# eVV_Radio.net
KiCad netlist of a schematic drawn in Altium Designer
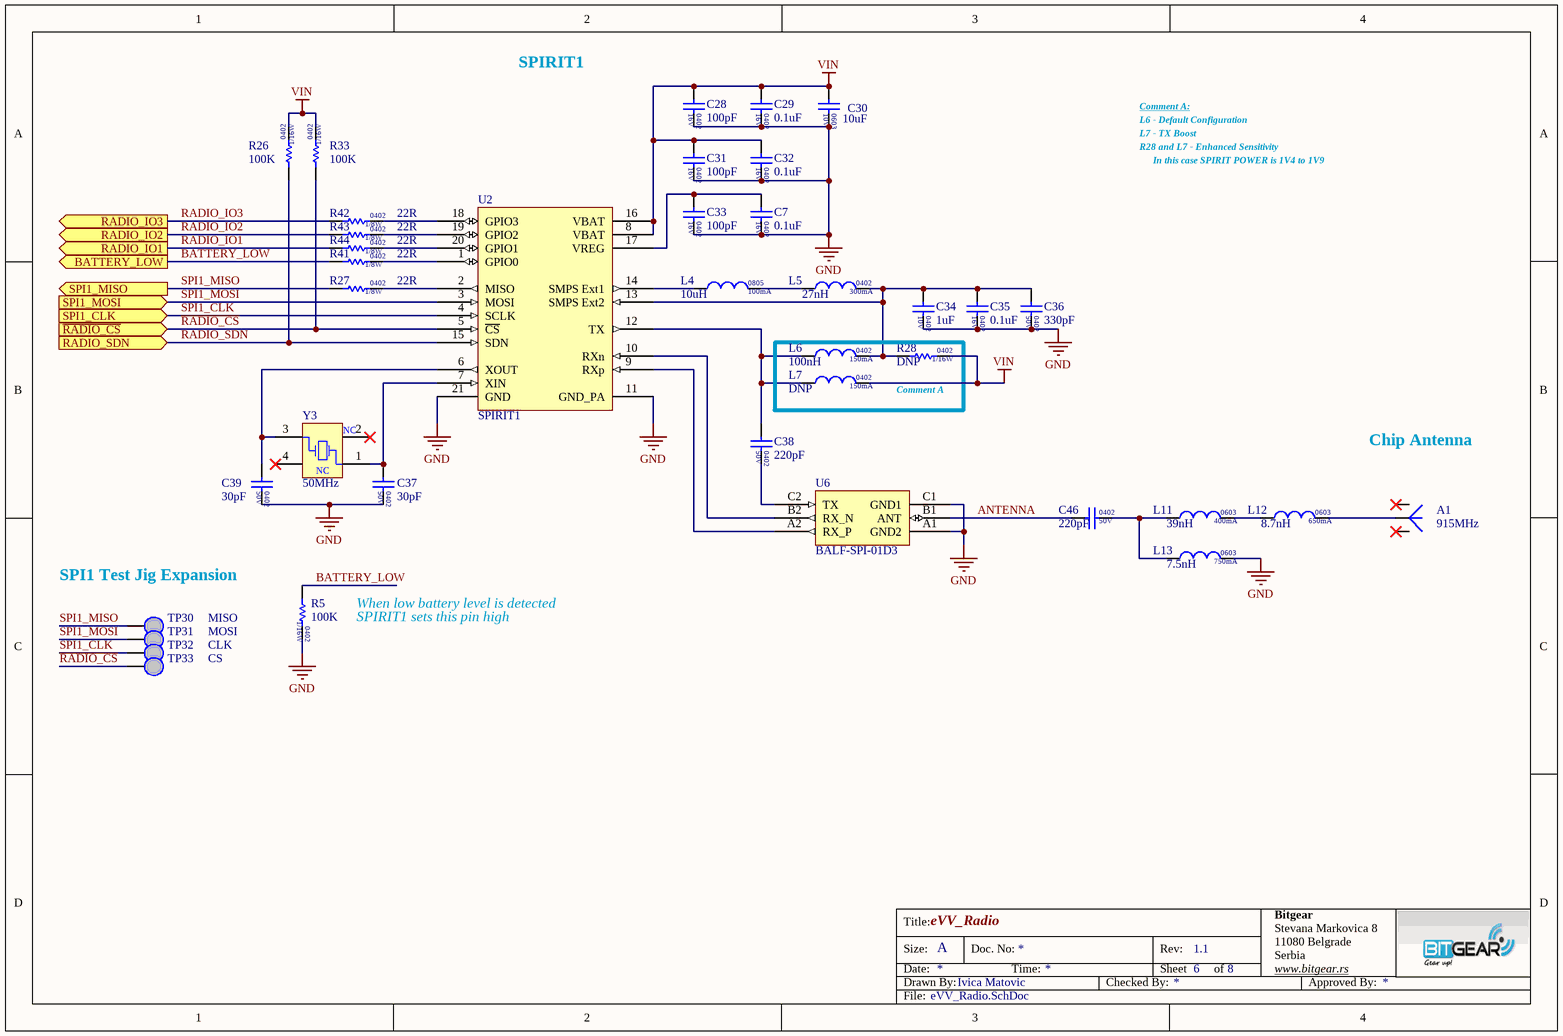
[diagram p0: eVV_Radio.SchDoc]

(export (version "E")
  (design (tool "Eeschema 10.0.6"))
  (components
    (comp (ref "A1")
      (value "915MHz")
      (footprint "MITSUBISHI_AM11DG-ST01")
      (description "Mitscubishi SMD Chip Antenna 3.0X10.5mm")
      (fields (field (name "MANUFACTURER") "Mitsubishi Materials"))
      (libsource (lib "ecoVENTV") (part "AM11DG-ST01"))
    )
    (comp (ref "C7")
      (value "0.1uF")
      (footprint "CAPC1005X60N")
      (description "CAP CER 0.1UF 0402 (1005) 16V X7R 10%")
      (fields (field (name "MANUFACTURER") "Murata Electronics North America"))
      (libsource (lib "ecoVENTV") (part "Cap-1005 (0402) CER 0.1UF 16V X7R 10%"))
    )
    (comp (ref "C28")
      (value "100pF")
      (footprint "CAPC1005X60N")
      (description "CAP CER 100PF 0402 (1005) 16V C0G 10%")
      (fields (field (name "MANUFACTURER") "Kemet"))
      (libsource (lib "ecoVENTV") (part "Cap-1005 (0402) CER 100PF 16V C0G 10%"))
    )
    (comp (ref "C29")
      (value "0.1uF")
      (footprint "CAPC1005X60N")
      (description "CAP CER 0.1UF 0402 (1005) 16V X7R 10%")
      (fields (field (name "MANUFACTURER") "Murata Electronics North America"))
      (libsource (lib "ecoVENTV") (part "Cap-1005 (0402) CER 0.1UF 16V X7R 10%"))
    )
    (comp (ref "C30")
      (value "10uF")
      (footprint "CAPC1608X95N")
      (description "Capacitor Ceramic 10uF 1608 (0603) 10V X5R 20%")
      (fields (field (name "MANUFACTURER") "Taiyo Yuden"))
      (libsource (lib "ecoVENTV") (part "Cap-1608 (0603) CER 10uF 10V X5R 20%"))
    )
    (comp (ref "C31")
      (value "100pF")
      (footprint "CAPC1005X60N")
      (description "CAP CER 100PF 0402 (1005) 16V C0G 10%")
      (fields (field (name "MANUFACTURER") "Kemet"))
      (libsource (lib "ecoVENTV") (part "Cap-1005 (0402) CER 100PF 16V C0G 10%"))
    )
    (comp (ref "C32")
      (value "0.1uF")
      (footprint "CAPC1005X60N")
      (description "CAP CER 0.1UF 0402 (1005) 16V X7R 10%")
      (fields (field (name "MANUFACTURER") "Murata Electronics North America"))
      (libsource (lib "ecoVENTV") (part "Cap-1005 (0402) CER 0.1UF 16V X7R 10%"))
    )
    (comp (ref "C33")
      (value "100pF")
      (footprint "CAPC1005X60N")
      (description "CAP CER 100PF 0402 (1005) 16V C0G 10%")
      (fields (field (name "MANUFACTURER") "Kemet"))
      (libsource (lib "ecoVENTV") (part "Cap-1005 (0402) CER 100PF 16V C0G 10%"))
    )
    (comp (ref "C34")
      (value "1uF")
      (footprint "CAPC1005X60N")
      (description "Cap-1005 (0402) CER 1uF 10V X5R 10%")
      (fields (field (name "MANUFACTURER") "Murata Electronics North America"))
      (libsource (lib "ecoVENTV") (part "Cap-1005 (0402) CER 1uF 10V X5R 10%"))
    )
    (comp (ref "C35")
      (value "0.1uF")
      (footprint "CAPC1005X60N")
      (description "CAP CER 0.1UF 0402 (1005) 16V X7R 10%")
      (fields (field (name "MANUFACTURER") "Murata Electronics North America"))
      (libsource (lib "ecoVENTV") (part "Cap-1005 (0402) CER 0.1UF 16V X7R 10%"))
    )
    (comp (ref "C36")
      (value "330pF")
      (footprint "CAPC1005X60N")
      (description "Cap-1005 (0402) CER 330pF 50V C0G 5%")
      (fields (field (name "MANUFACTURER") "Murata Electronics North America"))
      (libsource (lib "ecoVENTV") (part "Cap-1005 (0402) CER 330pF 50V C0G 5%"))
    )
    (comp (ref "C37")
      (value "30pF")
      (footprint "CAPC1005X60N")
      (description "CAP CER 30PF 50V 5% NP0 0402 (1005)")
      (fields (field (name "MANUFACTURER") "Murata Electronics North America"))
      (libsource (lib "ecoVENTV") (part "Cap-1005 (0402) CER 30pF 50V NP0 5%"))
    )
    (comp (ref "C38")
      (value "220pF")
      (footprint "CAPC1005X60N")
      (description "Cap-1005 (0402) CER 220pF 50V C0G 5%")
      (fields (field (name "MANUFACTURER") "Murata Electronics North America"))
      (libsource (lib "ecoVENTV") (part "Cap-1005 (0402) CER 220pF 50V C0G 5%"))
    )
    (comp (ref "C39")
      (value "30pF")
      (footprint "CAPC1005X60N")
      (description "CAP CER 30PF 50V 5% NP0 0402 (1005)")
      (fields (field (name "MANUFACTURER") "Murata Electronics North America"))
      (libsource (lib "ecoVENTV") (part "Cap-1005 (0402) CER 30pF 50V NP0 5%"))
    )
    (comp (ref "C46")
      (value "220pF")
      (footprint "CAPC1005X60N")
      (description "Cap-1005 (0402) CER 220pF 50V C0G 5%")
      (fields (field (name "MANUFACTURER") "Murata Electronics North America"))
      (libsource (lib "ecoVENTV") (part "Cap-1005 (0402) CER 220pF 50V C0G 5%"))
    )
    (comp (ref "L4")
      (value "10uH")
      (footprint "INDC2012X85N")
      (description "Inductor 10uH 100mA 20% 0805 SMD")
      (fields (field (name "MANUFACTURER") "Murata"))
      (libsource (lib "ecoVENTV") (part "Ind-2012 (0805) 10uH 100mA 20%"))
    )
    (comp (ref "L5")
      (value "27nH")
      (footprint "INDC1005X60N")
      (description "Inductor 27nH 300mA 5% 0402 SMD")
      (fields (field (name "MANUFACTURER") "Murata Electronics North America"))
      (libsource (lib "ecoVENTV") (part "Ind-1005 (0402) 27nH 300mA 5%"))
    )
    (comp (ref "L6")
      (value "100nH")
      (footprint "INDC1005X60N")
      (description "Inductor 100nH 150mA 5% 0402 SMD")
      (fields (field (name "MANUFACTURER") "Murata Electronics North America"))
      (libsource (lib "ecoVENTV") (part "Ind-1005 (0402) 100nH 150mA 5%"))
    )
    (comp (ref "L7")
      (value "DNP")
      (footprint "INDC1005X60N")
      (description "Inductor 100nH 150mA 5% 0402 SMD")
      (fields (field (name "MANUFACTURER") "Murata Electronics North America"))
      (libsource (lib "ecoVENTV") (part "Ind-1005 (0402) 100nH 150mA 5%"))
    )
    (comp (ref "L11")
      (value "39nH")
      (footprint "MURATA_LQW18A")
      (description "Inductor 39nH 400mA 2% 0603 SMD Wirewound")
      (fields (field (name "MANUFACTURER") "Murata Electronics North America"))
      (libsource (lib "ecoVENTV") (part "Ind-1608 (0603) 39nH 400mA 2%"))
    )
    (comp (ref "L12")
      (value "8.7nH")
      (footprint "MURATA_LQW18A")
      (description "Inductor 8.7nH 650mA 0.5nH 0603 SMD Wirewound")
      (fields (field (name "MANUFACTURER") "Murata Electronics North America"))
      (libsource (lib "ecoVENTV") (part "Ind-1608 (0603) 8.7nH 650mA 0.5nH"))
    )
    (comp (ref "L13")
      (value "7.5nH")
      (footprint "MURATA_LQW18A")
      (description "Inductor 7.5nH 750mA 0.5nH 0603 SMD Wirewound")
      (fields (field (name "MANUFACTURER") "Murata Electronics North America"))
      (libsource (lib "ecoVENTV") (part "Ind-1608 (0603) 7.5nH 750mA 0.5nH"))
    )
    (comp (ref "R5")
      (value "100K")
      (footprint "RESC1005X40AN")
      (description "Res-1005 (0402) 100 KOhm 1/16W 1%")
      (fields (field (name "MANUFACTURER") "Vishay Dale"))
      (libsource (lib "ecoVENTV") (part "Res-1005 (0402) 100 KOhm 1/16W 1%"))
    )
    (comp (ref "R26")
      (value "100K")
      (footprint "RESC1005X40AN")
      (description "Res-1005 (0402) 100 KOhm 1/16W 1%")
      (fields (field (name "MANUFACTURER") "Vishay Dale"))
      (libsource (lib "ecoVENTV") (part "Res-1005 (0402) 100 KOhm 1/16W 1%"))
    )
    (comp (ref "R27")
      (value "22R")
      (footprint "RESC1005X40AN")
      (description "Res-1005 (0402) 22 Ohm 1/8W 1%")
      (fields (field (name "MANUFACTURER") "Vishay Dale"))
      (libsource (lib "ecoVENTV") (part "Res-1005 (0402) 22 Ohm 1/8W 1%"))
    )
    (comp (ref "R28")
      (value "DNP")
      (footprint "RESC1005X40AN")
      (description "Res-1005 (0402) 0 Ohm 1/16W")
      (fields (field (name "MANUFACTURER") "Stackpole Electronics Inc"))
      (libsource (lib "ecoVENTV") (part "Res-1005 (0402) 0 Ohm 1/16W"))
    )
    (comp (ref "R33")
      (value "100K")
      (footprint "RESC1005X40AN")
      (description "Res-1005 (0402) 100 KOhm 1/16W 1%")
      (fields (field (name "MANUFACTURER") "Vishay Dale"))
      (libsource (lib "ecoVENTV") (part "Res-1005 (0402) 100 KOhm 1/16W 1%"))
    )
    (comp (ref "R41")
      (value "22R")
      (footprint "RESC1005X40AN")
      (description "Res-1005 (0402) 22 Ohm 1/8W 1%")
      (fields (field (name "MANUFACTURER") "Vishay Dale"))
      (libsource (lib "ecoVENTV") (part "Res-1005 (0402) 22 Ohm 1/8W 1%"))
    )
    (comp (ref "R42")
      (value "22R")
      (footprint "RESC1005X40AN")
      (description "Res-1005 (0402) 22 Ohm 1/8W 1%")
      (fields (field (name "MANUFACTURER") "Vishay Dale"))
      (libsource (lib "ecoVENTV") (part "Res-1005 (0402) 22 Ohm 1/8W 1%"))
    )
    (comp (ref "R43")
      (value "22R")
      (footprint "RESC1005X40AN")
      (description "Res-1005 (0402) 22 Ohm 1/8W 1%")
      (fields (field (name "MANUFACTURER") "Vishay Dale"))
      (libsource (lib "ecoVENTV") (part "Res-1005 (0402) 22 Ohm 1/8W 1%"))
    )
    (comp (ref "R44")
      (value "22R")
      (footprint "RESC1005X40AN")
      (description "Res-1005 (0402) 22 Ohm 1/8W 1%")
      (fields (field (name "MANUFACTURER") "Vishay Dale"))
      (libsource (lib "ecoVENTV") (part "Res-1005 (0402) 22 Ohm 1/8W 1%"))
    )
    (comp (ref "TP30")
      (value "MISO")
      (footprint "TEST_POINT_1MM")
      (description "Test point")
      (libsource (lib "ecoVENTV") (part "TP"))
    )
    (comp (ref "TP31")
      (value "MOSI")
      (footprint "TEST_POINT_1MM")
      (description "Test point")
      (libsource (lib "ecoVENTV") (part "TP"))
    )
    (comp (ref "TP32")
      (value "CLK")
      (footprint "TEST_POINT_1MM")
      (description "Test point")
      (libsource (lib "ecoVENTV") (part "TP"))
    )
    (comp (ref "TP33")
      (value "CS")
      (footprint "TEST_POINT_1MM")
      (description "Test point")
      (libsource (lib "ecoVENTV") (part "TP"))
    )
    (comp (ref "U2")
      (value "SPIRIT1")
      (footprint "QFN50P400X400X100-21N")
      (description "Low data rate, low power sub-1GHZ transceiver")
      (fields (field (name "MANUFACTURER") "ST Microelectronics"))
      (libsource (lib "ecoVENTV") (part "SPIRIT1"))
    )
    (comp (ref "U6")
      (value "BALF-SPI-01D3")
      (footprint "STM_BALF_SPI")
      (description "50 Ohm Balun to Spirit1 With Integrated Harmonic Filter")
      (fields (field (name "MANUFACTURER") "ST Microelectronics"))
      (libsource (lib "ecoVENTV") (part "BALF-SPI-01D3"))
    )
    (comp (ref "Y3")
      (value "50MHz")
      (footprint "AVX_CX3225GB50")
      (description "Crystal 50.000MHZ 3.2mm x 2.5mm 18pF")
      (fields (field (name "MANUFACTURER") "AVX Corp."))
      (libsource (lib "ecoVENTV") (part "CX3225GB50"))
    )
  )
  (nets
    (net (code "1") (name "/ANTENNA") (class "Default")
      (node (ref "C46") (pin "1") (pinfunction "1_1") (pintype "passive"))
      (node (ref "U6") (pin "B1") (pinfunction "ANT_B1") (pintype "bidirectional"))
    )
    (net (code "2") (name "/BATTERY_LOW") (class "Default")
      (node (ref "R41") (pin "2") (pinfunction "2_2") (pintype "passive"))
      (node (ref "R5") (pin "2") (pinfunction "2_2") (pintype "passive"))
    )
    (net (code "3") (name "/RADIO_IO1") (class "Default")
      (node (ref "R44") (pin "2") (pinfunction "2_2") (pintype "passive"))
    )
    (net (code "4") (name "/RADIO_IO2") (class "Default")
      (node (ref "R43") (pin "2") (pinfunction "2_2") (pintype "passive"))
    )
    (net (code "5") (name "/RADIO_IO3") (class "Default")
      (node (ref "R42") (pin "2") (pinfunction "2_2") (pintype "passive"))
    )
    (net (code "6") (name "/RADIO_SDN") (class "Default")
      (node (ref "R26") (pin "2") (pinfunction "2_2") (pintype "passive"))
      (node (ref "U2") (pin "15") (pinfunction "SDN_15") (pintype "input"))
    )
    (net (code "7") (name "/SPI1_CLK") (class "Default")
      (node (ref "TP32") (pin "1") (pinfunction "1_1") (pintype "passive"))
      (node (ref "U2") (pin "4") (pinfunction "SCLK_4") (pintype "input"))
    )
    (net (code "8") (name "/SPI1_MISO") (class "Default")
      (node (ref "R27") (pin "2") (pinfunction "2_2") (pintype "passive"))
      (node (ref "TP30") (pin "1") (pinfunction "1_1") (pintype "passive"))
    )
    (net (code "9") (name "/SPI1_MOSI") (class "Default")
      (node (ref "TP31") (pin "1") (pinfunction "1_1") (pintype "passive"))
      (node (ref "U2") (pin "3") (pinfunction "MOSI_3") (pintype "input"))
    )
    (net (code "10") (name "/~{RADIO_CS}") (class "Default")
      (node (ref "R33") (pin "2") (pinfunction "2_2") (pintype "passive"))
      (node (ref "TP33") (pin "1") (pinfunction "1_1") (pintype "passive"))
      (node (ref "U2") (pin "5") (pinfunction "~{CS}_5") (pintype "input"))
    )
    (net (code "11") (name "GND") (class "Default")
      (node (ref "C28") (pin "2") (pinfunction "2_2") (pintype "passive"))
      (node (ref "C29") (pin "2") (pinfunction "2_2") (pintype "passive"))
      (node (ref "C30") (pin "2") (pinfunction "2_2") (pintype "passive"))
      (node (ref "C31") (pin "2") (pinfunction "2_2") (pintype "passive"))
      (node (ref "C32") (pin "2") (pinfunction "2_2") (pintype "passive"))
      (node (ref "C33") (pin "2") (pinfunction "2_2") (pintype "passive"))
      (node (ref "C34") (pin "2") (pinfunction "2_2") (pintype "passive"))
      (node (ref "C35") (pin "2") (pinfunction "2_2") (pintype "passive"))
      (node (ref "C36") (pin "2") (pinfunction "2_2") (pintype "passive"))
      (node (ref "C37") (pin "2") (pinfunction "2_2") (pintype "passive"))
      (node (ref "C39") (pin "2") (pinfunction "2_2") (pintype "passive"))
      (node (ref "C7") (pin "2") (pinfunction "2_2") (pintype "passive"))
      (node (ref "L13") (pin "2") (pinfunction "2_2") (pintype "passive"))
      (node (ref "R5") (pin "1") (pinfunction "1_1") (pintype "passive"))
      (node (ref "U2") (pin "11") (pinfunction "GND_PA_11") (pintype "power_in"))
      (node (ref "U2") (pin "21") (pinfunction "GND_21") (pintype "power_in"))
      (node (ref "U6") (pin "A1") (pinfunction "GND2_A1") (pintype "power_in"))
      (node (ref "U6") (pin "C1") (pinfunction "GND1_C1") (pintype "power_in"))
    )
    (net (code "12") (name "Net-(A1-Pad1)") (class "Default")
      (node (ref "A1") (pin "1") (pinfunction "1_1") (pintype "passive"))
      (node (ref "L12") (pin "2") (pinfunction "2_2") (pintype "passive"))
    )
    (net (code "13") (name "Net-(C46-Pad2)") (class "Default")
      (node (ref "C46") (pin "2") (pinfunction "2_2") (pintype "passive"))
      (node (ref "L11") (pin "1") (pinfunction "1_1") (pintype "passive"))
      (node (ref "L13") (pin "1") (pinfunction "1_1") (pintype "passive"))
    )
    (net (code "14") (name "Net-(L4-Pad2)") (class "Default")
      (node (ref "L4") (pin "2") (pinfunction "2_2") (pintype "passive"))
      (node (ref "L5") (pin "1") (pinfunction "1_1") (pintype "passive"))
    )
    (net (code "15") (name "Net-(L11-Pad2)") (class "Default")
      (node (ref "L11") (pin "2") (pinfunction "2_2") (pintype "passive"))
      (node (ref "L12") (pin "1") (pinfunction "1_1") (pintype "passive"))
    )
    (net (code "16") (name "Net-(U2-GPIO0)") (class "Default")
      (node (ref "R41") (pin "1") (pinfunction "1_1") (pintype "passive"))
      (node (ref "U2") (pin "1") (pinfunction "GPIO0_1") (pintype "bidirectional"))
    )
    (net (code "17") (name "Net-(U2-GPIO1)") (class "Default")
      (node (ref "R44") (pin "1") (pinfunction "1_1") (pintype "passive"))
      (node (ref "U2") (pin "20") (pinfunction "GPIO1_20") (pintype "bidirectional"))
    )
    (net (code "18") (name "Net-(U2-GPIO2)") (class "Default")
      (node (ref "R43") (pin "1") (pinfunction "1_1") (pintype "passive"))
      (node (ref "U2") (pin "19") (pinfunction "GPIO2_19") (pintype "bidirectional"))
    )
    (net (code "19") (name "Net-(U2-GPIO3)") (class "Default")
      (node (ref "R42") (pin "1") (pinfunction "1_1") (pintype "passive"))
      (node (ref "U2") (pin "18") (pinfunction "GPIO3_18") (pintype "bidirectional"))
    )
    (net (code "20") (name "Net-(U2-MISO)") (class "Default")
      (node (ref "R27") (pin "1") (pinfunction "1_1") (pintype "passive"))
      (node (ref "U2") (pin "2") (pinfunction "MISO_2") (pintype "output"))
    )
    (net (code "21") (name "Net-(U2-RXn)") (class "Default")
      (node (ref "U2") (pin "10") (pinfunction "RXn_10") (pintype "input"))
      (node (ref "U6") (pin "B2") (pinfunction "RX_N_B2") (pintype "output"))
    )
    (net (code "22") (name "Net-(U2-RXp)") (class "Default")
      (node (ref "U2") (pin "9") (pinfunction "RXp_9") (pintype "input"))
      (node (ref "U6") (pin "A2") (pinfunction "RX_P_A2") (pintype "output"))
    )
    (net (code "23") (name "Net-(U2-SMPS_Ext1)") (class "Default")
      (node (ref "L4") (pin "1") (pinfunction "1_1") (pintype "passive"))
      (node (ref "U2") (pin "14") (pinfunction "SMPS_Ext1_14") (pintype "output"))
    )
    (net (code "24") (name "Net-(U2-SMPS_Ext2)") (class "Default")
      (node (ref "C34") (pin "1") (pinfunction "1_1") (pintype "passive"))
      (node (ref "C35") (pin "1") (pinfunction "1_1") (pintype "passive"))
      (node (ref "C36") (pin "1") (pinfunction "1_1") (pintype "passive"))
      (node (ref "L5") (pin "2") (pinfunction "2_2") (pintype "passive"))
      (node (ref "L6") (pin "2") (pinfunction "2_2") (pintype "passive"))
      (node (ref "R28") (pin "2") (pinfunction "2_2") (pintype "passive"))
      (node (ref "U2") (pin "13") (pinfunction "SMPS_Ext2_13") (pintype "input"))
    )
    (net (code "25") (name "Net-(U2-TX)") (class "Default")
      (node (ref "C38") (pin "1") (pinfunction "1_1") (pintype "passive"))
      (node (ref "L6") (pin "1") (pinfunction "1_1") (pintype "passive"))
      (node (ref "L7") (pin "1") (pinfunction "1_1") (pintype "passive"))
      (node (ref "U2") (pin "12") (pinfunction "TX_12") (pintype "output"))
    )
    (net (code "26") (name "Net-(U2-VREG)") (class "Default")
      (node (ref "C33") (pin "1") (pinfunction "1_1") (pintype "passive"))
      (node (ref "C7") (pin "1") (pinfunction "1_1") (pintype "passive"))
      (node (ref "U2") (pin "17") (pinfunction "VREG_17") (pintype "power_in"))
    )
    (net (code "27") (name "Net-(U2-XIN)") (class "Default")
      (node (ref "C37") (pin "1") (pinfunction "1_1") (pintype "passive"))
      (node (ref "U2") (pin "7") (pinfunction "XIN_7") (pintype "input"))
      (node (ref "Y3") (pin "1") (pinfunction "OSC1_1") (pintype "passive"))
    )
    (net (code "28") (name "Net-(U2-XOUT)") (class "Default")
      (node (ref "C39") (pin "1") (pinfunction "1_1") (pintype "passive"))
      (node (ref "U2") (pin "6") (pinfunction "XOUT_6") (pintype "output"))
      (node (ref "Y3") (pin "3") (pinfunction "OSC2_3") (pintype "passive"))
    )
    (net (code "29") (name "Net-(U6-TX)") (class "Default")
      (node (ref "C38") (pin "2") (pinfunction "2_2") (pintype "passive"))
      (node (ref "U6") (pin "C2") (pinfunction "TX_C2") (pintype "input"))
    )
    (net (code "30") (name "VIN") (class "Default")
      (node (ref "C28") (pin "1") (pinfunction "1_1") (pintype "passive"))
      (node (ref "C29") (pin "1") (pinfunction "1_1") (pintype "passive"))
      (node (ref "C30") (pin "1") (pinfunction "1_1") (pintype "passive"))
      (node (ref "C31") (pin "1") (pinfunction "1_1") (pintype "passive"))
      (node (ref "C32") (pin "1") (pinfunction "1_1") (pintype "passive"))
      (node (ref "L7") (pin "2") (pinfunction "2_2") (pintype "passive"))
      (node (ref "R26") (pin "1") (pinfunction "1_1") (pintype "passive"))
      (node (ref "R28") (pin "1") (pinfunction "1_1") (pintype "passive"))
      (node (ref "R33") (pin "1") (pinfunction "1_1") (pintype "passive"))
      (node (ref "U2") (pin "16") (pinfunction "VBAT_16") (pintype "power_in"))
      (node (ref "U2") (pin "8") (pinfunction "VBAT_8") (pintype "power_in"))
    )
    (net (code "31") (name "unconnected-(A1-Pad2)") (class "Default")
      (node (ref "A1") (pin "2") (pinfunction "2_2") (pintype "passive+no_connect"))
    )
    (net (code "32") (name "unconnected-(A1-Pad3)") (class "Default")
      (node (ref "A1") (pin "3") (pinfunction "3_3") (pintype "passive+no_connect"))
    )
    (net (code "33") (name "unconnected-(Y3-NC-Pad2)") (class "Default")
      (node (ref "Y3") (pin "2") (pinfunction "NC_2") (pintype "passive+no_connect"))
    )
    (net (code "34") (name "unconnected-(Y3-NC-Pad4)") (class "Default")
      (node (ref "Y3") (pin "4") (pinfunction "NC_4") (pintype "passive+no_connect"))
    )
  )
)
